# ESP32.net
KiCad netlist of a schematic drawn in Altium Designer
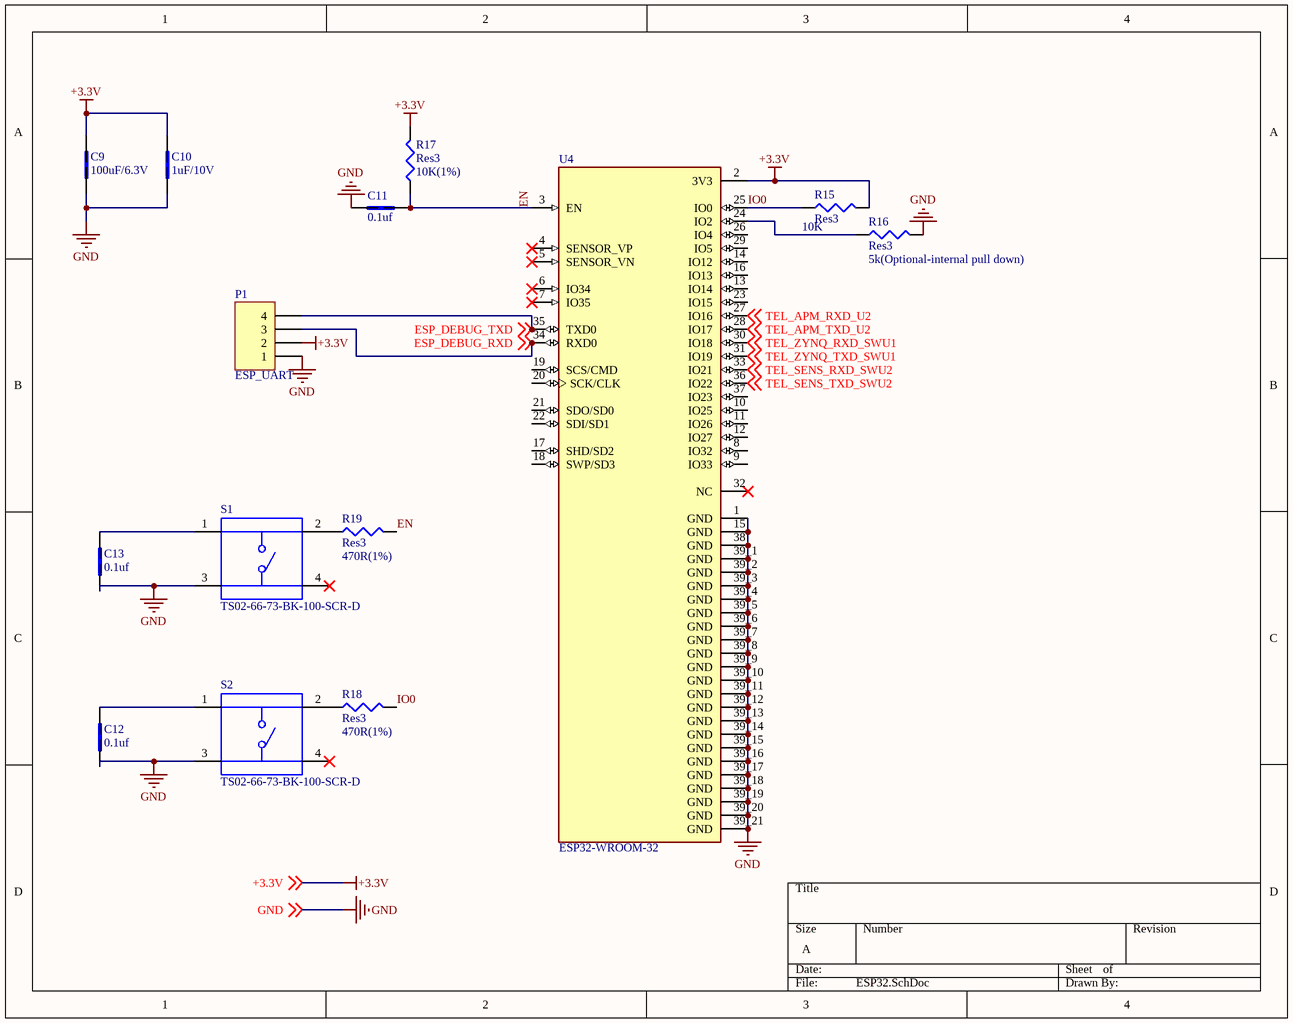
[diagram p0: ESP32.SchDoc]

(export (version "E")
  (design (tool "Eeschema 10.0.6"))
  (components
    (comp (ref "C9")
      (value "100uF/6.3V")
      (footprint "CAPC1608X90")
      (description "0.1ÂµF Â±10% 50V Ceramic Capacitor X7R 0603 (1608 Metric)")
      (fields (field (name "MP") "C0603C104K5RACTU") (field (name "DIGI-KEY_PART_NUMBER") "399-5089-1-ND"))
      (libsource (lib "") (part "C0603C104K5RACTU_1"))
    )
    (comp (ref "C10")
      (value "1uF/10V")
      (footprint "CAPC1608X90")
      (description "0.1ÂµF Â±10% 50V Ceramic Capacitor X7R 0603 (1608 Metric)")
      (fields (field (name "MP") "C0603C104K5RACTU") (field (name "DIGI-KEY_PART_NUMBER") "399-5089-1-ND"))
      (libsource (lib "") (part "C0603C104K5RACTU_1"))
    )
    (comp (ref "C11")
      (value "0.1uf")
      (footprint "CAPC1608X90")
      (description "0.1ÂµF Â±10% 50V Ceramic Capacitor X7R 0603 (1608 Metric)")
      (fields (field (name "MP") "C0603C104K5RACTU") (field (name "DIGI-KEY_PART_NUMBER") "399-5089-1-ND"))
      (libsource (lib "") (part "C0603C104K5RACTU_2"))
    )
    (comp (ref "C12")
      (value "0.1uf")
      (footprint "CAPC1608X90")
      (description "0.1ÂµF Â±10% 50V Ceramic Capacitor X7R 0603 (1608 Metric)")
      (fields (field (name "MP") "C0603C104K5RACTU") (field (name "DIGI-KEY_PART_NUMBER") "399-5089-1-ND"))
      (libsource (lib "C0603C104K5RACTU") (part "C0603C104K5RACTU"))
    )
    (comp (ref "C13")
      (value "0.1uf")
      (footprint "CAPC1608X90")
      (description "0.1ÂµF Â±10% 50V Ceramic Capacitor X7R 0603 (1608 Metric)")
      (fields (field (name "MP") "C0603C104K5RACTU") (field (name "DIGI-KEY_PART_NUMBER") "399-5089-1-ND"))
      (libsource (lib "C0603C104K5RACTU") (part "C0603C104K5RACTU"))
    )
    (comp (ref "P1")
      (value "ESP_UART")
      (footprint "HDR1X4")
      (description "Header, 4-Pin")
      (fields (field (name "PUBLISHER") "Altium Limited"))
      (libsource (lib "Miscellaneous Connectors") (part "Header 4"))
    )
    (comp (ref "R15")
      (value "Res3")
      (footprint "J1-0603")
      (description "Resistor")
      (fields (field (name "ALTIUM_VALUE") "10K") (field (name "PUBLISHER") "Altium Limited"))
      (libsource (lib "Miscellaneous Devices") (part "Res3"))
    )
    (comp (ref "R16")
      (value "Res3")
      (footprint "J1-0603")
      (description "Resistor")
      (fields
        (field (name "ALTIUM_VALUE") "5k(Optional-internal pull down)")
        (field (name "PUBLISHER") "Altium Limited")
      )
      (libsource (lib "Miscellaneous Devices") (part "Res3"))
    )
    (comp (ref "R17")
      (value "Res3")
      (footprint "J1-0603")
      (description "Resistor")
      (fields (field (name "ALTIUM_VALUE") "10K(1%)") (field (name "PUBLISHER") "Altium Limited"))
      (libsource (lib "Miscellaneous Devices") (part "Res3"))
    )
    (comp (ref "R18")
      (value "Res3")
      (footprint "J1-0603")
      (description "Resistor")
      (fields (field (name "ALTIUM_VALUE") "470R(1%)") (field (name "PUBLISHER") "Altium Limited"))
      (libsource (lib "Miscellaneous Devices") (part "Res3"))
    )
    (comp (ref "R19")
      (value "Res3")
      (footprint "J1-0603")
      (description "Resistor")
      (fields (field (name "ALTIUM_VALUE") "470R(1%)") (field (name "PUBLISHER") "Altium Limited"))
      (libsource (lib "Miscellaneous Devices") (part "Res3"))
    )
    (comp (ref "S1")
      (value "TS02-66-73-BK-100-SCR-D")
      (footprint "SW_TS02-66-73-BK-100-SCR-D")
      (fields (field (name "MF") "{'manufacturer': u'CUI'}"))
      (libsource (lib "TS02-66-73-BK-100-SCR-D") (part "TS02-66-73-BK-100-SCR-D"))
    )
    (comp (ref "S2")
      (value "TS02-66-73-BK-100-SCR-D")
      (footprint "SW_TS02-66-73-BK-100-SCR-D")
      (fields (field (name "MF") "{'manufacturer': u'CUI'}"))
      (libsource (lib "TS02-66-73-BK-100-SCR-D") (part "TS02-66-73-BK-100-SCR-D"))
    )
    (comp (ref "U4")
      (value "ESP32-WROOM-32")
      (footprint "MODULE_ESP32-WROOM-32")
      (libsource (lib "ESP32-WROOM-32") (part "ESP32-WROOM-32"))
    )
  )
  (nets
    (net (code "1") (name "+3.3V") (class "Default")
      (node (ref "C10") (pin "2") (pinfunction "2_2") (pintype "passive"))
      (node (ref "C9") (pin "2") (pinfunction "2_2") (pintype "passive"))
      (node (ref "P1") (pin "2") (pinfunction "2_2") (pintype "passive"))
      (node (ref "R15") (pin "2") (pinfunction "2_2") (pintype "passive"))
      (node (ref "R17") (pin "2") (pinfunction "2_2") (pintype "passive"))
      (node (ref "U4") (pin "2") (pinfunction "3V3_2") (pintype "power_in"))
    )
    (net (code "2") (name "/EN") (class "Default")
      (node (ref "C11") (pin "1") (pinfunction "1_1") (pintype "passive"))
      (node (ref "R17") (pin "1") (pinfunction "1_1") (pintype "passive"))
      (node (ref "R19") (pin "2") (pinfunction "2_2") (pintype "passive"))
      (node (ref "U4") (pin "3") (pinfunction "EN_3") (pintype "input"))
    )
    (net (code "3") (name "/IO0") (class "Default")
      (node (ref "R15") (pin "1") (pinfunction "1_1") (pintype "passive"))
      (node (ref "R18") (pin "2") (pinfunction "2_2") (pintype "passive"))
      (node (ref "U4") (pin "25") (pinfunction "IO0_25") (pintype "bidirectional"))
    )
    (net (code "4") (name "ESP_DEBUG_RXD") (class "Default")
      (node (ref "P1") (pin "3") (pinfunction "3_3") (pintype "passive"))
      (node (ref "U4") (pin "34") (pinfunction "RXD0_34") (pintype "bidirectional"))
    )
    (net (code "5") (name "ESP_DEBUG_TXD") (class "Default")
      (node (ref "P1") (pin "4") (pinfunction "4_4") (pintype "passive"))
      (node (ref "U4") (pin "35") (pinfunction "TXD0_35") (pintype "bidirectional"))
    )
    (net (code "6") (name "GND") (class "Default")
      (node (ref "C10") (pin "1") (pinfunction "1_1") (pintype "passive"))
      (node (ref "C11") (pin "2") (pinfunction "2_2") (pintype "passive"))
      (node (ref "C12") (pin "2") (pinfunction "2_2") (pintype "passive"))
      (node (ref "C13") (pin "2") (pinfunction "2_2") (pintype "passive"))
      (node (ref "C9") (pin "1") (pinfunction "1_1") (pintype "passive"))
      (node (ref "P1") (pin "1") (pinfunction "1_1") (pintype "passive"))
      (node (ref "R16") (pin "2") (pinfunction "2_2") (pintype "passive"))
      (node (ref "S1") (pin "3") (pinfunction "3_3") (pintype "passive"))
      (node (ref "S2") (pin "3") (pinfunction "3_3") (pintype "passive"))
      (node (ref "U4") (pin "1") (pinfunction "GND_1") (pintype "power_in"))
      (node (ref "U4") (pin "15") (pinfunction "GND_15") (pintype "power_in"))
      (node (ref "U4") (pin "38") (pinfunction "GND_38") (pintype "power_in"))
      (node (ref "U4") (pin "39_1") (pinfunction "GND_39_1") (pintype "power_in"))
      (node (ref "U4") (pin "39_10") (pinfunction "GND_39_10") (pintype "power_in"))
      (node (ref "U4") (pin "39_11") (pinfunction "GND_39_11") (pintype "power_in"))
      (node (ref "U4") (pin "39_12") (pinfunction "GND_39_12") (pintype "power_in"))
      (node (ref "U4") (pin "39_13") (pinfunction "GND_39_13") (pintype "power_in"))
      (node (ref "U4") (pin "39_14") (pinfunction "GND_39_14") (pintype "power_in"))
      (node (ref "U4") (pin "39_15") (pinfunction "GND_39_15") (pintype "power_in"))
      (node (ref "U4") (pin "39_16") (pinfunction "GND_39_16") (pintype "power_in"))
      (node (ref "U4") (pin "39_17") (pinfunction "GND_39_17") (pintype "power_in"))
      (node (ref "U4") (pin "39_18") (pinfunction "GND_39_18") (pintype "power_in"))
      (node (ref "U4") (pin "39_19") (pinfunction "GND_39_19") (pintype "power_in"))
      (node (ref "U4") (pin "39_2") (pinfunction "GND_39_2") (pintype "power_in"))
      (node (ref "U4") (pin "39_20") (pinfunction "GND_39_20") (pintype "power_in"))
      (node (ref "U4") (pin "39_21") (pinfunction "GND_39_21") (pintype "power_in"))
      (node (ref "U4") (pin "39_3") (pinfunction "GND_39_3") (pintype "power_in"))
      (node (ref "U4") (pin "39_4") (pinfunction "GND_39_4") (pintype "power_in"))
      (node (ref "U4") (pin "39_5") (pinfunction "GND_39_5") (pintype "power_in"))
      (node (ref "U4") (pin "39_6") (pinfunction "GND_39_6") (pintype "power_in"))
      (node (ref "U4") (pin "39_7") (pinfunction "GND_39_7") (pintype "power_in"))
      (node (ref "U4") (pin "39_8") (pinfunction "GND_39_8") (pintype "power_in"))
      (node (ref "U4") (pin "39_9") (pinfunction "GND_39_9") (pintype "power_in"))
    )
    (net (code "7") (name "Net-(C12-Pad1)") (class "Default")
      (node (ref "C12") (pin "1") (pinfunction "1_1") (pintype "passive"))
      (node (ref "S2") (pin "1") (pinfunction "1_1") (pintype "passive"))
    )
    (net (code "8") (name "Net-(C13-Pad1)") (class "Default")
      (node (ref "C13") (pin "1") (pinfunction "1_1") (pintype "passive"))
      (node (ref "S1") (pin "1") (pinfunction "1_1") (pintype "passive"))
    )
    (net (code "9") (name "Net-(R18-Pad1)") (class "Default")
      (node (ref "R18") (pin "1") (pinfunction "1_1") (pintype "passive"))
      (node (ref "S2") (pin "2") (pinfunction "2_2") (pintype "passive"))
    )
    (net (code "10") (name "Net-(R19-Pad1)") (class "Default")
      (node (ref "R19") (pin "1") (pinfunction "1_1") (pintype "passive"))
      (node (ref "S1") (pin "2") (pinfunction "2_2") (pintype "passive"))
    )
    (net (code "11") (name "Net-(U4-IO2)") (class "Default")
      (node (ref "R16") (pin "1") (pinfunction "1_1") (pintype "passive"))
      (node (ref "U4") (pin "24") (pinfunction "IO2_24") (pintype "bidirectional"))
    )
    (net (code "12") (name "TEL_APM_RXD_U2") (class "Default")
      (node (ref "U4") (pin "27") (pinfunction "IO16_27") (pintype "bidirectional"))
    )
    (net (code "13") (name "TEL_APM_TXD_U2") (class "Default")
      (node (ref "U4") (pin "28") (pinfunction "IO17_28") (pintype "bidirectional"))
    )
    (net (code "14") (name "TEL_SENS_RXD_SWU2") (class "Default")
      (node (ref "U4") (pin "33") (pinfunction "IO21_33") (pintype "bidirectional"))
    )
    (net (code "15") (name "TEL_SENS_TXD_SWU2") (class "Default")
      (node (ref "U4") (pin "36") (pinfunction "IO22_36") (pintype "bidirectional"))
    )
    (net (code "16") (name "TEL_ZYNQ_RXD_SWU1") (class "Default")
      (node (ref "U4") (pin "30") (pinfunction "IO18_30") (pintype "bidirectional"))
    )
    (net (code "17") (name "TEL_ZYNQ_TXD_SWU1") (class "Default")
      (node (ref "U4") (pin "31") (pinfunction "IO19_31") (pintype "bidirectional"))
    )
    (net (code "18") (name "unconnected-(S1-Pad4)") (class "Default")
      (node (ref "S1") (pin "4") (pinfunction "4_4") (pintype "passive+no_connect"))
    )
    (net (code "19") (name "unconnected-(S2-Pad4)") (class "Default")
      (node (ref "S2") (pin "4") (pinfunction "4_4") (pintype "passive+no_connect"))
    )
    (net (code "20") (name "unconnected-(U4-IO4-Pad26)") (class "Default")
      (node (ref "U4") (pin "26") (pinfunction "IO4_26") (pintype "bidirectional"))
    )
    (net (code "21") (name "unconnected-(U4-IO5-Pad29)") (class "Default")
      (node (ref "U4") (pin "29") (pinfunction "IO5_29") (pintype "bidirectional"))
    )
    (net (code "22") (name "unconnected-(U4-IO12-Pad14)") (class "Default")
      (node (ref "U4") (pin "14") (pinfunction "IO12_14") (pintype "bidirectional"))
    )
    (net (code "23") (name "unconnected-(U4-IO13-Pad16)") (class "Default")
      (node (ref "U4") (pin "16") (pinfunction "IO13_16") (pintype "bidirectional"))
    )
    (net (code "24") (name "unconnected-(U4-IO14-Pad13)") (class "Default")
      (node (ref "U4") (pin "13") (pinfunction "IO14_13") (pintype "bidirectional"))
    )
    (net (code "25") (name "unconnected-(U4-IO15-Pad23)") (class "Default")
      (node (ref "U4") (pin "23") (pinfunction "IO15_23") (pintype "bidirectional"))
    )
    (net (code "26") (name "unconnected-(U4-IO23-Pad37)") (class "Default")
      (node (ref "U4") (pin "37") (pinfunction "IO23_37") (pintype "bidirectional"))
    )
    (net (code "27") (name "unconnected-(U4-IO25-Pad10)") (class "Default")
      (node (ref "U4") (pin "10") (pinfunction "IO25_10") (pintype "bidirectional"))
    )
    (net (code "28") (name "unconnected-(U4-IO26-Pad11)") (class "Default")
      (node (ref "U4") (pin "11") (pinfunction "IO26_11") (pintype "bidirectional"))
    )
    (net (code "29") (name "unconnected-(U4-IO27-Pad12)") (class "Default")
      (node (ref "U4") (pin "12") (pinfunction "IO27_12") (pintype "bidirectional"))
    )
    (net (code "30") (name "unconnected-(U4-IO32-Pad8)") (class "Default")
      (node (ref "U4") (pin "8") (pinfunction "IO32_8") (pintype "bidirectional"))
    )
    (net (code "31") (name "unconnected-(U4-IO33-Pad9)") (class "Default")
      (node (ref "U4") (pin "9") (pinfunction "IO33_9") (pintype "bidirectional"))
    )
    (net (code "32") (name "unconnected-(U4-IO34-Pad6)") (class "Default")
      (node (ref "U4") (pin "6") (pinfunction "IO34_6") (pintype "input+no_connect"))
    )
    (net (code "33") (name "unconnected-(U4-IO35-Pad7)") (class "Default")
      (node (ref "U4") (pin "7") (pinfunction "IO35_7") (pintype "input+no_connect"))
    )
    (net (code "34") (name "unconnected-(U4-NC-Pad32)") (class "Default")
      (node (ref "U4") (pin "32") (pinfunction "NC_32") (pintype "passive+no_connect"))
    )
    (net (code "35") (name "unconnected-(U4-SCK{slash}CLK-Pad20)") (class "Default")
      (node (ref "U4") (pin "20") (pinfunction "SCK/CLK_20") (pintype "bidirectional"))
    )
    (net (code "36") (name "unconnected-(U4-SCS{slash}CMD-Pad19)") (class "Default")
      (node (ref "U4") (pin "19") (pinfunction "SCS/CMD_19") (pintype "bidirectional"))
    )
    (net (code "37") (name "unconnected-(U4-SDI{slash}SD1-Pad22)") (class "Default")
      (node (ref "U4") (pin "22") (pinfunction "SDI/SD1_22") (pintype "bidirectional"))
    )
    (net (code "38") (name "unconnected-(U4-SDO{slash}SD0-Pad21)") (class "Default")
      (node (ref "U4") (pin "21") (pinfunction "SDO/SD0_21") (pintype "bidirectional"))
    )
    (net (code "39") (name "unconnected-(U4-SENSOR_VN-Pad5)") (class "Default")
      (node (ref "U4") (pin "5") (pinfunction "SENSOR_VN_5") (pintype "input+no_connect"))
    )
    (net (code "40") (name "unconnected-(U4-SENSOR_VP-Pad4)") (class "Default")
      (node (ref "U4") (pin "4") (pinfunction "SENSOR_VP_4") (pintype "input+no_connect"))
    )
    (net (code "41") (name "unconnected-(U4-SHD{slash}SD2-Pad17)") (class "Default")
      (node (ref "U4") (pin "17") (pinfunction "SHD/SD2_17") (pintype "bidirectional"))
    )
    (net (code "42") (name "unconnected-(U4-SWP{slash}SD3-Pad18)") (class "Default")
      (node (ref "U4") (pin "18") (pinfunction "SWP/SD3_18") (pintype "bidirectional"))
    )
  )
)
